# SSD_PINOUT.net
KiCad netlist of a schematic drawn in Altium Designer
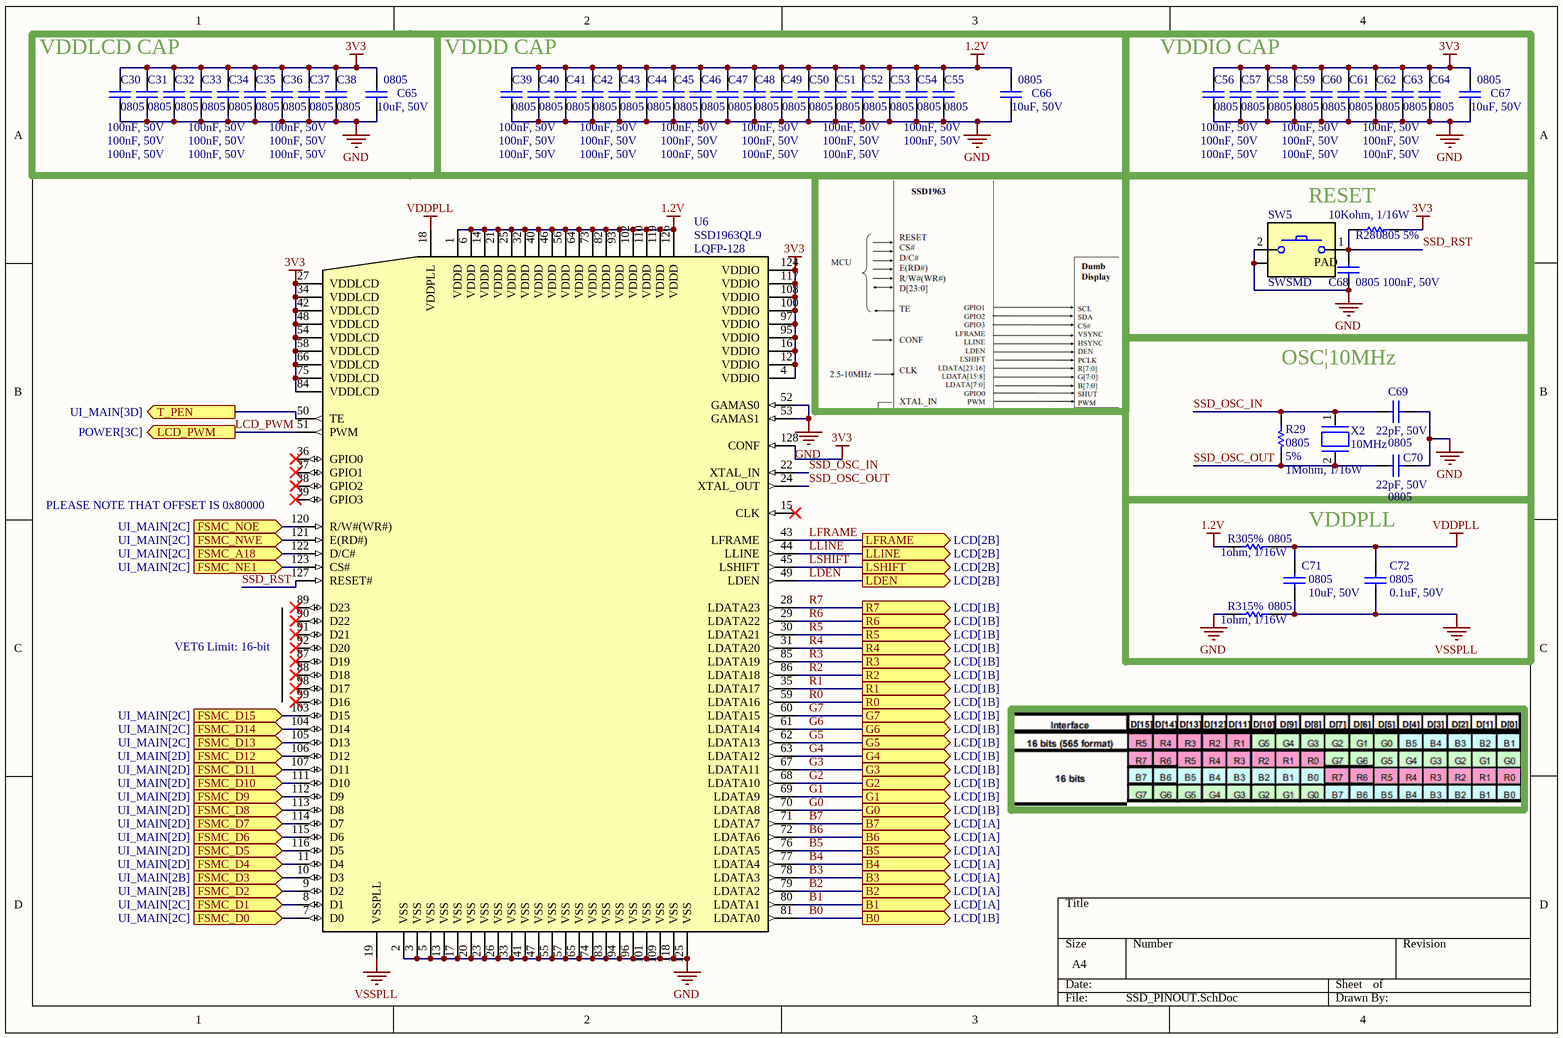
[diagram p0: SSD_PINOUT.SchDoc]

(export (version "E")
  (design (tool "Eeschema 10.0.6"))
  (components
    (comp (ref "C30")
      (value "100nF, 50V")
      (footprint "C_0805")
      (description "CAP_0805")
      (fields (field (name "PACKAGE") "0805"))
      (libsource (lib "DisplayLib") (part "CAP_0805"))
    )
    (comp (ref "C31")
      (value "100nF, 50V")
      (footprint "C_0805")
      (description "CAP_0805")
      (fields (field (name "PACKAGE") "0805"))
      (libsource (lib "DisplayLib") (part "CAP_0805"))
    )
    (comp (ref "C32")
      (value "100nF, 50V")
      (footprint "C_0805")
      (description "CAP_0805")
      (fields (field (name "PACKAGE") "0805"))
      (libsource (lib "DisplayLib") (part "CAP_0805"))
    )
    (comp (ref "C33")
      (value "100nF, 50V")
      (footprint "C_0805")
      (description "CAP_0805")
      (fields (field (name "PACKAGE") "0805"))
      (libsource (lib "DisplayLib") (part "CAP_0805"))
    )
    (comp (ref "C34")
      (value "100nF, 50V")
      (footprint "C_0805")
      (description "CAP_0805")
      (fields (field (name "PACKAGE") "0805"))
      (libsource (lib "DisplayLib") (part "CAP_0805"))
    )
    (comp (ref "C35")
      (value "100nF, 50V")
      (footprint "C_0805")
      (description "CAP_0805")
      (fields (field (name "PACKAGE") "0805"))
      (libsource (lib "DisplayLib") (part "CAP_0805"))
    )
    (comp (ref "C36")
      (value "100nF, 50V")
      (footprint "C_0805")
      (description "CAP_0805")
      (fields (field (name "PACKAGE") "0805"))
      (libsource (lib "DisplayLib") (part "CAP_0805"))
    )
    (comp (ref "C37")
      (value "100nF, 50V")
      (footprint "C_0805")
      (description "CAP_0805")
      (fields (field (name "PACKAGE") "0805"))
      (libsource (lib "DisplayLib") (part "CAP_0805"))
    )
    (comp (ref "C38")
      (value "100nF, 50V")
      (footprint "C_0805")
      (description "CAP_0805")
      (fields (field (name "PACKAGE") "0805"))
      (libsource (lib "DisplayLib") (part "CAP_0805"))
    )
    (comp (ref "C39")
      (value "100nF, 50V")
      (footprint "C_0805")
      (description "CAP_0805")
      (fields (field (name "PACKAGE") "0805"))
      (libsource (lib "DisplayLib") (part "CAP_0805"))
    )
    (comp (ref "C40")
      (value "100nF, 50V")
      (footprint "C_0805")
      (description "CAP_0805")
      (fields (field (name "PACKAGE") "0805"))
      (libsource (lib "DisplayLib") (part "CAP_0805"))
    )
    (comp (ref "C41")
      (value "100nF, 50V")
      (footprint "C_0805")
      (description "CAP_0805")
      (fields (field (name "PACKAGE") "0805"))
      (libsource (lib "DisplayLib") (part "CAP_0805"))
    )
    (comp (ref "C42")
      (value "100nF, 50V")
      (footprint "C_0805")
      (description "CAP_0805")
      (fields (field (name "PACKAGE") "0805"))
      (libsource (lib "DisplayLib") (part "CAP_0805"))
    )
    (comp (ref "C43")
      (value "100nF, 50V")
      (footprint "C_0805")
      (description "CAP_0805")
      (fields (field (name "PACKAGE") "0805"))
      (libsource (lib "DisplayLib") (part "CAP_0805"))
    )
    (comp (ref "C44")
      (value "100nF, 50V")
      (footprint "C_0805")
      (description "CAP_0805")
      (fields (field (name "PACKAGE") "0805"))
      (libsource (lib "DisplayLib") (part "CAP_0805"))
    )
    (comp (ref "C45")
      (value "100nF, 50V")
      (footprint "C_0805")
      (description "CAP_0805")
      (fields (field (name "PACKAGE") "0805"))
      (libsource (lib "DisplayLib") (part "CAP_0805"))
    )
    (comp (ref "C46")
      (value "100nF, 50V")
      (footprint "C_0805")
      (description "CAP_0805")
      (fields (field (name "PACKAGE") "0805"))
      (libsource (lib "DisplayLib") (part "CAP_0805"))
    )
    (comp (ref "C47")
      (value "100nF, 50V")
      (footprint "C_0805")
      (description "CAP_0805")
      (fields (field (name "PACKAGE") "0805"))
      (libsource (lib "DisplayLib") (part "CAP_0805"))
    )
    (comp (ref "C48")
      (value "100nF, 50V")
      (footprint "C_0805")
      (description "CAP_0805")
      (fields (field (name "PACKAGE") "0805"))
      (libsource (lib "DisplayLib") (part "CAP_0805"))
    )
    (comp (ref "C49")
      (value "100nF, 50V")
      (footprint "C_0805")
      (description "CAP_0805")
      (fields (field (name "PACKAGE") "0805"))
      (libsource (lib "DisplayLib") (part "CAP_0805"))
    )
    (comp (ref "C50")
      (value "100nF, 50V")
      (footprint "C_0805")
      (description "CAP_0805")
      (fields (field (name "PACKAGE") "0805"))
      (libsource (lib "DisplayLib") (part "CAP_0805"))
    )
    (comp (ref "C51")
      (value "100nF, 50V")
      (footprint "C_0805")
      (description "CAP_0805")
      (fields (field (name "PACKAGE") "0805"))
      (libsource (lib "DisplayLib") (part "CAP_0805"))
    )
    (comp (ref "C52")
      (value "100nF, 50V")
      (footprint "C_0805")
      (description "CAP_0805")
      (fields (field (name "PACKAGE") "0805"))
      (libsource (lib "DisplayLib") (part "CAP_0805"))
    )
    (comp (ref "C53")
      (value "100nF, 50V")
      (footprint "C_0805")
      (description "CAP_0805")
      (fields (field (name "PACKAGE") "0805"))
      (libsource (lib "DisplayLib") (part "CAP_0805"))
    )
    (comp (ref "C54")
      (value "100nF, 50V")
      (footprint "C_0805")
      (description "CAP_0805")
      (fields (field (name "PACKAGE") "0805"))
      (libsource (lib "DisplayLib") (part "CAP_0805"))
    )
    (comp (ref "C55")
      (value "100nF, 50V")
      (footprint "C_0805")
      (description "CAP_0805")
      (fields (field (name "PACKAGE") "0805"))
      (libsource (lib "DisplayLib") (part "CAP_0805"))
    )
    (comp (ref "C56")
      (value "100nF, 50V")
      (footprint "C_0805")
      (description "CAP_0805")
      (fields (field (name "PACKAGE") "0805"))
      (libsource (lib "DisplayLib") (part "CAP_0805"))
    )
    (comp (ref "C57")
      (value "100nF, 50V")
      (footprint "C_0805")
      (description "CAP_0805")
      (fields (field (name "PACKAGE") "0805"))
      (libsource (lib "DisplayLib") (part "CAP_0805"))
    )
    (comp (ref "C58")
      (value "100nF, 50V")
      (footprint "C_0805")
      (description "CAP_0805")
      (fields (field (name "PACKAGE") "0805"))
      (libsource (lib "DisplayLib") (part "CAP_0805"))
    )
    (comp (ref "C59")
      (value "100nF, 50V")
      (footprint "C_0805")
      (description "CAP_0805")
      (fields (field (name "PACKAGE") "0805"))
      (libsource (lib "DisplayLib") (part "CAP_0805"))
    )
    (comp (ref "C60")
      (value "100nF, 50V")
      (footprint "C_0805")
      (description "CAP_0805")
      (fields (field (name "PACKAGE") "0805"))
      (libsource (lib "DisplayLib") (part "CAP_0805"))
    )
    (comp (ref "C61")
      (value "100nF, 50V")
      (footprint "C_0805")
      (description "CAP_0805")
      (fields (field (name "PACKAGE") "0805"))
      (libsource (lib "DisplayLib") (part "CAP_0805"))
    )
    (comp (ref "C62")
      (value "100nF, 50V")
      (footprint "C_0805")
      (description "CAP_0805")
      (fields (field (name "PACKAGE") "0805"))
      (libsource (lib "DisplayLib") (part "CAP_0805"))
    )
    (comp (ref "C63")
      (value "100nF, 50V")
      (footprint "C_0805")
      (description "CAP_0805")
      (fields (field (name "PACKAGE") "0805"))
      (libsource (lib "DisplayLib") (part "CAP_0805"))
    )
    (comp (ref "C64")
      (value "100nF, 50V")
      (footprint "C_0805")
      (description "CAP_0805")
      (fields (field (name "PACKAGE") "0805"))
      (libsource (lib "DisplayLib") (part "CAP_0805"))
    )
    (comp (ref "C65")
      (value "10uF, 50V")
      (footprint "C_0805")
      (description "CAP_0805")
      (fields (field (name "PACKAGE") "0805"))
      (libsource (lib "DisplayLib") (part "CAP_0805"))
    )
    (comp (ref "C66")
      (value "10uF, 50V")
      (footprint "C_0805")
      (description "CAP_0805")
      (fields (field (name "PACKAGE") "0805"))
      (libsource (lib "DisplayLib") (part "CAP_0805"))
    )
    (comp (ref "C67")
      (value "10uF, 50V")
      (footprint "C_0805")
      (description "CAP_0805")
      (fields (field (name "PACKAGE") "0805"))
      (libsource (lib "DisplayLib") (part "CAP_0805"))
    )
    (comp (ref "C68")
      (value "100nF, 50V")
      (footprint "C_0805")
      (description "CAP_0805")
      (fields (field (name "PACKAGE") "0805"))
      (libsource (lib "DisplayLib") (part "CAP_0805"))
    )
    (comp (ref "C69")
      (value "22pF, 50V")
      (footprint "C_0805")
      (description "CAP_0805")
      (fields (field (name "PACKAGE") "0805"))
      (libsource (lib "DisplayLib") (part "CAP_0805"))
    )
    (comp (ref "C70")
      (value "22pF, 50V")
      (footprint "C_0805")
      (description "CAP_0805")
      (fields (field (name "PACKAGE") "0805"))
      (libsource (lib "DisplayLib") (part "CAP_0805"))
    )
    (comp (ref "C71")
      (value "10uF, 50V")
      (footprint "C_0805")
      (description "CAP_0805")
      (fields (field (name "PACKAGE") "0805"))
      (libsource (lib "DisplayLib") (part "CAP_0805"))
    )
    (comp (ref "C72")
      (value "0.1uF, 50V")
      (footprint "C_0805")
      (description "CAP_0805")
      (fields (field (name "PACKAGE") "0805"))
      (libsource (lib "DisplayLib") (part "CAP_0805"))
    )
    (comp (ref "R28")
      (value "10Kohm, 1/16W")
      (footprint "R_0805")
      (description "RES_0805")
      (fields (field (name "PACKAGE") "0805") (field (name "ACC") "5%"))
      (libsource (lib "DisplayLib") (part "RES_0805"))
    )
    (comp (ref "R29")
      (value "1Mohm, 1/16W")
      (footprint "R_0805")
      (description "RES_0805")
      (fields (field (name "PACKAGE") "0805") (field (name "ACC") "5%"))
      (libsource (lib "DisplayLib") (part "RES_0805"))
    )
    (comp (ref "R30")
      (value "1ohm, 1/16W")
      (footprint "R_0805")
      (description "RES_0805")
      (fields (field (name "PACKAGE") "0805") (field (name "ACC") "5%"))
      (libsource (lib "DisplayLib") (part "RES_0805"))
    )
    (comp (ref "R31")
      (value "1ohm, 1/16W")
      (footprint "R_0805")
      (description "RES_0805")
      (fields (field (name "PACKAGE") "0805") (field (name "ACC") "5%"))
      (libsource (lib "DisplayLib") (part "RES_0805"))
    )
    (comp (ref "SW5")
      (value "SWSMD")
      (footprint "SW_SMD")
      (description "SW_SMD")
      (libsource (lib "DisplayLib") (part "SWSMD"))
    )
    (comp (ref "U6")
      (value "SSD1963QL9")
      (footprint "PKG_LQFP-128")
      (description "1215KB Embedded Display SRAM\r\nLCD Display Controller")
      (fields (field (name "PACKAGE") "LQFP-128"))
      (libsource (lib "DisplayLib") (part "SSD1963QL9"))
    )
    (comp (ref "X2")
      (value "10MHz")
      (footprint "PKG_HC49-S")
      (description "Crystal, 10 MHz, -30 to 85 degC, 3.2 x 2.5 x 0.9 mm SMD")
      (libsource (lib "DisplayLib") (part "XTAL_8MHZ"))
    )
  )
  (nets
    (net (code "1") (name "/B0") (class "Default")
      (node (ref "U6") (pin "81") (pinfunction "LDATA0_81") (pintype "output"))
    )
    (net (code "2") (name "/B1") (class "Default")
      (node (ref "U6") (pin "80") (pinfunction "LDATA1_80") (pintype "output"))
    )
    (net (code "3") (name "/B2") (class "Default")
      (node (ref "U6") (pin "79") (pinfunction "LDATA2_79") (pintype "output"))
    )
    (net (code "4") (name "/B3") (class "Default")
      (node (ref "U6") (pin "78") (pinfunction "LDATA3_78") (pintype "output"))
    )
    (net (code "5") (name "/B4") (class "Default")
      (node (ref "U6") (pin "77") (pinfunction "LDATA4_77") (pintype "output"))
    )
    (net (code "6") (name "/B5") (class "Default")
      (node (ref "U6") (pin "76") (pinfunction "LDATA5_76") (pintype "output"))
    )
    (net (code "7") (name "/B6") (class "Default")
      (node (ref "U6") (pin "72") (pinfunction "LDATA6_72") (pintype "output"))
    )
    (net (code "8") (name "/B7") (class "Default")
      (node (ref "U6") (pin "71") (pinfunction "LDATA7_71") (pintype "output"))
    )
    (net (code "9") (name "/FSMC_A18") (class "Default")
      (node (ref "U6") (pin "122") (pinfunction "D/C#_122") (pintype "input"))
    )
    (net (code "10") (name "/FSMC_D0") (class "Default")
      (node (ref "U6") (pin "7") (pinfunction "D0_7") (pintype "bidirectional"))
    )
    (net (code "11") (name "/FSMC_D1") (class "Default")
      (node (ref "U6") (pin "8") (pinfunction "D1_8") (pintype "bidirectional"))
    )
    (net (code "12") (name "/FSMC_D2") (class "Default")
      (node (ref "U6") (pin "9") (pinfunction "D2_9") (pintype "bidirectional"))
    )
    (net (code "13") (name "/FSMC_D3") (class "Default")
      (node (ref "U6") (pin "10") (pinfunction "D3_10") (pintype "bidirectional"))
    )
    (net (code "14") (name "/FSMC_D4") (class "Default")
      (node (ref "U6") (pin "11") (pinfunction "D4_11") (pintype "bidirectional"))
    )
    (net (code "15") (name "/FSMC_D5") (class "Default")
      (node (ref "U6") (pin "116") (pinfunction "D5_116") (pintype "bidirectional"))
    )
    (net (code "16") (name "/FSMC_D6") (class "Default")
      (node (ref "U6") (pin "115") (pinfunction "D6_115") (pintype "bidirectional"))
    )
    (net (code "17") (name "/FSMC_D7") (class "Default")
      (node (ref "U6") (pin "114") (pinfunction "D7_114") (pintype "bidirectional"))
    )
    (net (code "18") (name "/FSMC_D8") (class "Default")
      (node (ref "U6") (pin "113") (pinfunction "D8_113") (pintype "bidirectional"))
    )
    (net (code "19") (name "/FSMC_D9") (class "Default")
      (node (ref "U6") (pin "112") (pinfunction "D9_112") (pintype "bidirectional"))
    )
    (net (code "20") (name "/FSMC_D10") (class "Default")
      (node (ref "U6") (pin "111") (pinfunction "D10_111") (pintype "bidirectional"))
    )
    (net (code "21") (name "/FSMC_D11") (class "Default")
      (node (ref "U6") (pin "107") (pinfunction "D11_107") (pintype "bidirectional"))
    )
    (net (code "22") (name "/FSMC_D12") (class "Default")
      (node (ref "U6") (pin "106") (pinfunction "D12_106") (pintype "bidirectional"))
    )
    (net (code "23") (name "/FSMC_D13") (class "Default")
      (node (ref "U6") (pin "105") (pinfunction "D13_105") (pintype "bidirectional"))
    )
    (net (code "24") (name "/FSMC_D14") (class "Default")
      (node (ref "U6") (pin "104") (pinfunction "D14_104") (pintype "bidirectional"))
    )
    (net (code "25") (name "/FSMC_D15") (class "Default")
      (node (ref "U6") (pin "103") (pinfunction "D15_103") (pintype "bidirectional"))
    )
    (net (code "26") (name "/FSMC_NE1") (class "Default")
      (node (ref "U6") (pin "123") (pinfunction "CS#_123") (pintype "input"))
    )
    (net (code "27") (name "/FSMC_NOE") (class "Default")
      (node (ref "U6") (pin "120") (pinfunction "R/W#(WR#)_120") (pintype "input"))
    )
    (net (code "28") (name "/FSMC_NWE") (class "Default")
      (node (ref "U6") (pin "121") (pinfunction "E(RD#)_121") (pintype "input"))
    )
    (net (code "29") (name "/G0") (class "Default")
      (node (ref "U6") (pin "70") (pinfunction "LDATA8_70") (pintype "output"))
    )
    (net (code "30") (name "/G1") (class "Default")
      (node (ref "U6") (pin "69") (pinfunction "LDATA9_69") (pintype "output"))
    )
    (net (code "31") (name "/G2") (class "Default")
      (node (ref "U6") (pin "68") (pinfunction "LDATA10_68") (pintype "output"))
    )
    (net (code "32") (name "/G3") (class "Default")
      (node (ref "U6") (pin "67") (pinfunction "LDATA11_67") (pintype "output"))
    )
    (net (code "33") (name "/G4") (class "Default")
      (node (ref "U6") (pin "63") (pinfunction "LDATA12_63") (pintype "output"))
    )
    (net (code "34") (name "/G5") (class "Default")
      (node (ref "U6") (pin "62") (pinfunction "LDATA13_62") (pintype "output"))
    )
    (net (code "35") (name "/G6") (class "Default")
      (node (ref "U6") (pin "61") (pinfunction "LDATA14_61") (pintype "output"))
    )
    (net (code "36") (name "/G7") (class "Default")
      (node (ref "U6") (pin "60") (pinfunction "LDATA15_60") (pintype "output"))
    )
    (net (code "37") (name "/LCD_PWM") (class "Default")
      (node (ref "U6") (pin "51") (pinfunction "PWM_51") (pintype "output"))
    )
    (net (code "38") (name "/LDEN") (class "Default")
      (node (ref "U6") (pin "49") (pinfunction "LDEN_49") (pintype "output"))
    )
    (net (code "39") (name "/LFRAME") (class "Default")
      (node (ref "U6") (pin "43") (pinfunction "LFRAME_43") (pintype "output"))
    )
    (net (code "40") (name "/LLINE") (class "Default")
      (node (ref "U6") (pin "44") (pinfunction "LLINE_44") (pintype "output"))
    )
    (net (code "41") (name "/LSHIFT") (class "Default")
      (node (ref "U6") (pin "45") (pinfunction "LSHIFT_45") (pintype "output"))
    )
    (net (code "42") (name "/R0") (class "Default")
      (node (ref "U6") (pin "59") (pinfunction "LDATA16_59") (pintype "output"))
    )
    (net (code "43") (name "/R1") (class "Default")
      (node (ref "U6") (pin "35") (pinfunction "LDATA17_35") (pintype "output"))
    )
    (net (code "44") (name "/R2") (class "Default")
      (node (ref "U6") (pin "86") (pinfunction "LDATA18_86") (pintype "output"))
    )
    (net (code "45") (name "/R3") (class "Default")
      (node (ref "U6") (pin "85") (pinfunction "LDATA19_85") (pintype "output"))
    )
    (net (code "46") (name "/R4") (class "Default")
      (node (ref "U6") (pin "31") (pinfunction "LDATA20_31") (pintype "output"))
    )
    (net (code "47") (name "/R5") (class "Default")
      (node (ref "U6") (pin "30") (pinfunction "LDATA21_30") (pintype "output"))
    )
    (net (code "48") (name "/R6") (class "Default")
      (node (ref "U6") (pin "29") (pinfunction "LDATA22_29") (pintype "output"))
    )
    (net (code "49") (name "/R7") (class "Default")
      (node (ref "U6") (pin "28") (pinfunction "LDATA23_28") (pintype "output"))
    )
    (net (code "50") (name "/SSD_OSC_IN") (class "Default")
      (node (ref "C69") (pin "2") (pinfunction "2_2") (pintype "passive"))
      (node (ref "R29") (pin "1") (pinfunction "1_1") (pintype "passive"))
      (node (ref "U6") (pin "22") (pinfunction "XTAL_IN_22") (pintype "input"))
      (node (ref "X2") (pin "1") (pinfunction "1_1") (pintype "passive"))
    )
    (net (code "51") (name "/SSD_OSC_OUT") (class "Default")
      (node (ref "C70") (pin "2") (pinfunction "2_2") (pintype "passive"))
      (node (ref "R29") (pin "2") (pinfunction "2_2") (pintype "passive"))
      (node (ref "U6") (pin "24") (pinfunction "XTAL_OUT_24") (pintype "output"))
      (node (ref "X2") (pin "2") (pinfunction "2_2") (pintype "passive"))
    )
    (net (code "52") (name "/SSD_RST") (class "Default")
      (node (ref "C68") (pin "2") (pinfunction "2_2") (pintype "passive"))
      (node (ref "R28") (pin "2") (pinfunction "2_2") (pintype "passive"))
      (node (ref "SW5") (pin "1") (pinfunction "1_1") (pintype "passive"))
      (node (ref "U6") (pin "127") (pinfunction "RESET#_127") (pintype "input"))
    )
    (net (code "53") (name "/T_PEN") (class "Default")
      (node (ref "U6") (pin "50") (pinfunction "TE_50") (pintype "output"))
    )
    (net (code "54") (name "1.2V") (class "Default")
      (node (ref "C39") (pin "2") (pinfunction "2_2") (pintype "passive"))
      (node (ref "C40") (pin "2") (pinfunction "2_2") (pintype "passive"))
      (node (ref "C41") (pin "2") (pinfunction "2_2") (pintype "passive"))
      (node (ref "C42") (pin "2") (pinfunction "2_2") (pintype "passive"))
      (node (ref "C43") (pin "2") (pinfunction "2_2") (pintype "passive"))
      (node (ref "C44") (pin "2") (pinfunction "2_2") (pintype "passive"))
      (node (ref "C45") (pin "2") (pinfunction "2_2") (pintype "passive"))
      (node (ref "C46") (pin "2") (pinfunction "2_2") (pintype "passive"))
      (node (ref "C47") (pin "2") (pinfunction "2_2") (pintype "passive"))
      (node (ref "C48") (pin "2") (pinfunction "2_2") (pintype "passive"))
      (node (ref "C49") (pin "2") (pinfunction "2_2") (pintype "passive"))
      (node (ref "C50") (pin "2") (pinfunction "2_2") (pintype "passive"))
      (node (ref "C51") (pin "2") (pinfunction "2_2") (pintype "passive"))
      (node (ref "C52") (pin "2") (pinfunction "2_2") (pintype "passive"))
      (node (ref "C53") (pin "2") (pinfunction "2_2") (pintype "passive"))
      (node (ref "C54") (pin "2") (pinfunction "2_2") (pintype "passive"))
      (node (ref "C55") (pin "2") (pinfunction "2_2") (pintype "passive"))
      (node (ref "C66") (pin "2") (pinfunction "2_2") (pintype "passive"))
      (node (ref "R30") (pin "2") (pinfunction "2_2") (pintype "passive"))
      (node (ref "U6") (pin "1") (pinfunction "VDDD_1") (pintype "power_in"))
      (node (ref "U6") (pin "102") (pinfunction "VDDD_102") (pintype "power_in"))
      (node (ref "U6") (pin "110") (pinfunction "VDDD_110") (pintype "power_in"))
      (node (ref "U6") (pin "119") (pinfunction "VDDD_119") (pintype "power_in"))
      (node (ref "U6") (pin "126") (pinfunction "VDDD_126") (pintype "power_in"))
      (node (ref "U6") (pin "14") (pinfunction "VDDD_14") (pintype "power_in"))
      (node (ref "U6") (pin "21") (pinfunction "VDDD_21") (pintype "power_in"))
      (node (ref "U6") (pin "25") (pinfunction "VDDD_25") (pintype "power_in"))
      (node (ref "U6") (pin "32") (pinfunction "VDDD_32") (pintype "power_in"))
      (node (ref "U6") (pin "40") (pinfunction "VDDD_40") (pintype "power_in"))
      (node (ref "U6") (pin "46") (pinfunction "VDDD_46") (pintype "power_in"))
      (node (ref "U6") (pin "56") (pinfunction "VDDD_56") (pintype "power_in"))
      (node (ref "U6") (pin "6") (pinfunction "VDDD_6") (pintype "power_in"))
      (node (ref "U6") (pin "64") (pinfunction "VDDD_64") (pintype "power_in"))
      (node (ref "U6") (pin "73") (pinfunction "VDDD_73") (pintype "power_in"))
      (node (ref "U6") (pin "82") (pinfunction "VDDD_82") (pintype "power_in"))
      (node (ref "U6") (pin "93") (pinfunction "VDDD_93") (pintype "power_in"))
    )
    (net (code "55") (name "3V3") (class "Default")
      (node (ref "C30") (pin "2") (pinfunction "2_2") (pintype "passive"))
      (node (ref "C31") (pin "2") (pinfunction "2_2") (pintype "passive"))
      (node (ref "C32") (pin "2") (pinfunction "2_2") (pintype "passive"))
      (node (ref "C33") (pin "2") (pinfunction "2_2") (pintype "passive"))
      (node (ref "C34") (pin "2") (pinfunction "2_2") (pintype "passive"))
      (node (ref "C35") (pin "2") (pinfunction "2_2") (pintype "passive"))
      (node (ref "C36") (pin "2") (pinfunction "2_2") (pintype "passive"))
      (node (ref "C37") (pin "2") (pinfunction "2_2") (pintype "passive"))
      (node (ref "C38") (pin "2") (pinfunction "2_2") (pintype "passive"))
      (node (ref "C56") (pin "2") (pinfunction "2_2") (pintype "passive"))
      (node (ref "C57") (pin "2") (pinfunction "2_2") (pintype "passive"))
      (node (ref "C58") (pin "2") (pinfunction "2_2") (pintype "passive"))
      (node (ref "C59") (pin "2") (pinfunction "2_2") (pintype "passive"))
      (node (ref "C60") (pin "2") (pinfunction "2_2") (pintype "passive"))
      (node (ref "C61") (pin "2") (pinfunction "2_2") (pintype "passive"))
      (node (ref "C62") (pin "2") (pinfunction "2_2") (pintype "passive"))
      (node (ref "C63") (pin "2") (pinfunction "2_2") (pintype "passive"))
      (node (ref "C64") (pin "2") (pinfunction "2_2") (pintype "passive"))
      (node (ref "C65") (pin "2") (pinfunction "2_2") (pintype "passive"))
      (node (ref "C67") (pin "2") (pinfunction "2_2") (pintype "passive"))
      (node (ref "R28") (pin "1") (pinfunction "1_1") (pintype "passive"))
      (node (ref "U6") (pin "100") (pinfunction "VDDIO_100") (pintype "power_in"))
      (node (ref "U6") (pin "108") (pinfunction "VDDIO_108") (pintype "power_in"))
      (node (ref "U6") (pin "117") (pinfunction "VDDIO_117") (pintype "power_in"))
      (node (ref "U6") (pin "12") (pinfunction "VDDIO_12") (pintype "power_in"))
      (node (ref "U6") (pin "124") (pinfunction "VDDIO_124") (pintype "power_in"))
      (node (ref "U6") (pin "128") (pinfunction "CONF_128") (pintype "input"))
      (node (ref "U6") (pin "16") (pinfunction "VDDIO_16") (pintype "power_in"))
      (node (ref "U6") (pin "27") (pinfunction "VDDLCD_27") (pintype "power_in"))
      (node (ref "U6") (pin "34") (pinfunction "VDDLCD_34") (pintype "power_in"))
      (node (ref "U6") (pin "4") (pinfunction "VDDIO_4") (pintype "power_in"))
      (node (ref "U6") (pin "42") (pinfunction "VDDLCD_42") (pintype "power_in"))
      (node (ref "U6") (pin "48") (pinfunction "VDDLCD_48") (pintype "power_in"))
      (node (ref "U6") (pin "54") (pinfunction "VDDLCD_54") (pintype "power_in"))
      (node (ref "U6") (pin "58") (pinfunction "VDDLCD_58") (pintype "power_in"))
      (node (ref "U6") (pin "66") (pinfunction "VDDLCD_66") (pintype "power_in"))
      (node (ref "U6") (pin "75") (pinfunction "VDDLCD_75") (pintype "power_in"))
      (node (ref "U6") (pin "84") (pinfunction "VDDLCD_84") (pintype "power_in"))
      (node (ref "U6") (pin "95") (pinfunction "VDDIO_95") (pintype "power_in"))
      (node (ref "U6") (pin "97") (pinfunction "VDDIO_97") (pintype "power_in"))
    )
    (net (code "56") (name "GND") (class "Default")
      (node (ref "C30") (pin "1") (pinfunction "1_1") (pintype "passive"))
      (node (ref "C31") (pin "1") (pinfunction "1_1") (pintype "passive"))
      (node (ref "C32") (pin "1") (pinfunction "1_1") (pintype "passive"))
      (node (ref "C33") (pin "1") (pinfunction "1_1") (pintype "passive"))
      (node (ref "C34") (pin "1") (pinfunction "1_1") (pintype "passive"))
      (node (ref "C35") (pin "1") (pinfunction "1_1") (pintype "passive"))
      (node (ref "C36") (pin "1") (pinfunction "1_1") (pintype "passive"))
      (node (ref "C37") (pin "1") (pinfunction "1_1") (pintype "passive"))
      (node (ref "C38") (pin "1") (pinfunction "1_1") (pintype "passive"))
      (node (ref "C39") (pin "1") (pinfunction "1_1") (pintype "passive"))
      (node (ref "C40") (pin "1") (pinfunction "1_1") (pintype "passive"))
      (node (ref "C41") (pin "1") (pinfunction "1_1") (pintype "passive"))
      (node (ref "C42") (pin "1") (pinfunction "1_1") (pintype "passive"))
      (node (ref "C43") (pin "1") (pinfunction "1_1") (pintype "passive"))
      (node (ref "C44") (pin "1") (pinfunction "1_1") (pintype "passive"))
      (node (ref "C45") (pin "1") (pinfunction "1_1") (pintype "passive"))
      (node (ref "C46") (pin "1") (pinfunction "1_1") (pintype "passive"))
      (node (ref "C47") (pin "1") (pinfunction "1_1") (pintype "passive"))
      (node (ref "C48") (pin "1") (pinfunction "1_1") (pintype "passive"))
      (node (ref "C49") (pin "1") (pinfunction "1_1") (pintype "passive"))
      (node (ref "C50") (pin "1") (pinfunction "1_1") (pintype "passive"))
      (node (ref "C51") (pin "1") (pinfunction "1_1") (pintype "passive"))
      (node (ref "C52") (pin "1") (pinfunction "1_1") (pintype "passive"))
      (node (ref "C53") (pin "1") (pinfunction "1_1") (pintype "passive"))
      (node (ref "C54") (pin "1") (pinfunction "1_1") (pintype "passive"))
      (node (ref "C55") (pin "1") (pinfunction "1_1") (pintype "passive"))
      (node (ref "C56") (pin "1") (pinfunction "1_1") (pintype "passive"))
      (node (ref "C57") (pin "1") (pinfunction "1_1") (pintype "passive"))
      (node (ref "C58") (pin "1") (pinfunction "1_1") (pintype "passive"))
      (node (ref "C59") (pin "1") (pinfunction "1_1") (pintype "passive"))
      (node (ref "C60") (pin "1") (pinfunction "1_1") (pintype "passive"))
      (node (ref "C61") (pin "1") (pinfunction "1_1") (pintype "passive"))
      (node (ref "C62") (pin "1") (pinfunction "1_1") (pintype "passive"))
      (node (ref "C63") (pin "1") (pinfunction "1_1") (pintype "passive"))
      (node (ref "C64") (pin "1") (pinfunction "1_1") (pintype "passive"))
      (node (ref "C65") (pin "1") (pinfunction "1_1") (pintype "passive"))
      (node (ref "C66") (pin "1") (pinfunction "1_1") (pintype "passive"))
      (node (ref "C67") (pin "1") (pinfunction "1_1") (pintype "passive"))
      (node (ref "C68") (pin "1") (pinfunction "1_1") (pintype "passive"))
      (node (ref "C69") (pin "1") (pinfunction "1_1") (pintype "passive"))
      (node (ref "C70") (pin "1") (pinfunction "1_1") (pintype "passive"))
      (node (ref "R31") (pin "2") (pinfunction "2_2") (pintype "passive"))
      (node (ref "SW5") (pin "0") (pinfunction "PAD_0") (pintype "passive"))
      (node (ref "SW5") (pin "2") (pinfunction "2_2") (pintype "passive"))
      (node (ref "U6") (pin "101") (pinfunction "VSS_101") (pintype "power_in"))
      (node (ref "U6") (pin "109") (pinfunction "VSS_109") (pintype "power_in"))
      (node (ref "U6") (pin "118") (pinfunction "VSS_118") (pintype "power_in"))
      (node (ref "U6") (pin "125") (pinfunction "VSS_125") (pintype "power_in"))
      (node (ref "U6") (pin "13") (pinfunction "VSS_13") (pintype "power_in"))
      (node (ref "U6") (pin "17") (pinfunction "VSS_17") (pintype "power_in"))
      (node (ref "U6") (pin "2") (pinfunction "VSS_2") (pintype "power_in"))
      (node (ref "U6") (pin "20") (pinfunction "VSS_20") (pintype "power_in"))
      (node (ref "U6") (pin "23") (pinfunction "VSS_23") (pintype "power_in"))
      (node (ref "U6") (pin "26") (pinfunction "VSS_26") (pintype "power_in"))
      (node (ref "U6") (pin "3") (pinfunction "VSS_3") (pintype "power_in"))
      (node (ref "U6") (pin "33") (pinfunction "VSS_33") (pintype "power_in"))
      (node (ref "U6") (pin "41") (pinfunction "VSS_41") (pintype "power_in"))
      (node (ref "U6") (pin "47") (pinfunction "VSS_47") (pintype "power_in"))
      (node (ref "U6") (pin "5") (pinfunction "VSS_5") (pintype "power_in"))
      (node (ref "U6") (pin "52") (pinfunction "GAMAS0_52") (pintype "input"))
      (node (ref "U6") (pin "53") (pinfunction "GAMAS1_53") (pintype "input"))
      (node (ref "U6") (pin "55") (pinfunction "VSS_55") (pintype "power_in"))
      (node (ref "U6") (pin "57") (pinfunction "VSS_57") (pintype "power_in"))
      (node (ref "U6") (pin "65") (pinfunction "VSS_65") (pintype "power_in"))
      (node (ref "U6") (pin "74") (pinfunction "VSS_74") (pintype "power_in"))
      (node (ref "U6") (pin "83") (pinfunction "VSS_83") (pintype "power_in"))
      (node (ref "U6") (pin "94") (pinfunction "VSS_94") (pintype "power_in"))
      (node (ref "U6") (pin "96") (pinfunction "VSS_96") (pintype "power_in"))
    )
    (net (code "57") (name "VDDPLL") (class "Default")
      (node (ref "C71") (pin "2") (pinfunction "2_2") (pintype "passive"))
      (node (ref "C72") (pin "2") (pinfunction "2_2") (pintype "passive"))
      (node (ref "R30") (pin "1") (pinfunction "1_1") (pintype "passive"))
      (node (ref "U6") (pin "18") (pinfunction "VDDPLL_18") (pintype "power_in"))
    )
    (net (code "58") (name "VSSPLL") (class "Default")
      (node (ref "C71") (pin "1") (pinfunction "1_1") (pintype "passive"))
      (node (ref "C72") (pin "1") (pinfunction "1_1") (pintype "passive"))
      (node (ref "R31") (pin "1") (pinfunction "1_1") (pintype "passive"))
      (node (ref "U6") (pin "19") (pinfunction "VSSPLL_19") (pintype "power_in"))
    )
    (net (code "59") (name "unconnected-(U6-CLK-Pad15)") (class "Default")
      (node (ref "U6") (pin "15") (pinfunction "CLK_15") (pintype "input+no_connect"))
    )
    (net (code "60") (name "unconnected-(U6-D16-Pad99)") (class "Default")
      (node (ref "U6") (pin "99") (pinfunction "D16_99") (pintype "bidirectional+no_connect"))
    )
    (net (code "61") (name "unconnected-(U6-D17-Pad98)") (class "Default")
      (node (ref "U6") (pin "98") (pinfunction "D17_98") (pintype "bidirectional+no_connect"))
    )
    (net (code "62") (name "unconnected-(U6-D18-Pad88)") (class "Default")
      (node (ref "U6") (pin "88") (pinfunction "D18_88") (pintype "bidirectional+no_connect"))
    )
    (net (code "63") (name "unconnected-(U6-D19-Pad87)") (class "Default")
      (node (ref "U6") (pin "87") (pinfunction "D19_87") (pintype "bidirectional+no_connect"))
    )
    (net (code "64") (name "unconnected-(U6-D20-Pad92)") (class "Default")
      (node (ref "U6") (pin "92") (pinfunction "D20_92") (pintype "bidirectional+no_connect"))
    )
    (net (code "65") (name "unconnected-(U6-D21-Pad91)") (class "Default")
      (node (ref "U6") (pin "91") (pinfunction "D21_91") (pintype "bidirectional+no_connect"))
    )
    (net (code "66") (name "unconnected-(U6-D22-Pad90)") (class "Default")
      (node (ref "U6") (pin "90") (pinfunction "D22_90") (pintype "bidirectional+no_connect"))
    )
    (net (code "67") (name "unconnected-(U6-D23-Pad89)") (class "Default")
      (node (ref "U6") (pin "89") (pinfunction "D23_89") (pintype "bidirectional+no_connect"))
    )
    (net (code "68") (name "unconnected-(U6-GPIO0-Pad36)") (class "Default")
      (node (ref "U6") (pin "36") (pinfunction "GPIO0_36") (pintype "bidirectional+no_connect"))
    )
    (net (code "69") (name "unconnected-(U6-GPIO1-Pad37)") (class "Default")
      (node (ref "U6") (pin "37") (pinfunction "GPIO1_37") (pintype "bidirectional+no_connect"))
    )
    (net (code "70") (name "unconnected-(U6-GPIO2-Pad38)") (class "Default")
      (node (ref "U6") (pin "38") (pinfunction "GPIO2_38") (pintype "bidirectional+no_connect"))
    )
    (net (code "71") (name "unconnected-(U6-GPIO3-Pad39)") (class "Default")
      (node (ref "U6") (pin "39") (pinfunction "GPIO3_39") (pintype "bidirectional+no_connect"))
    )
  )
)
